# Key.net
KiCad netlist of a schematic drawn in EAGLE
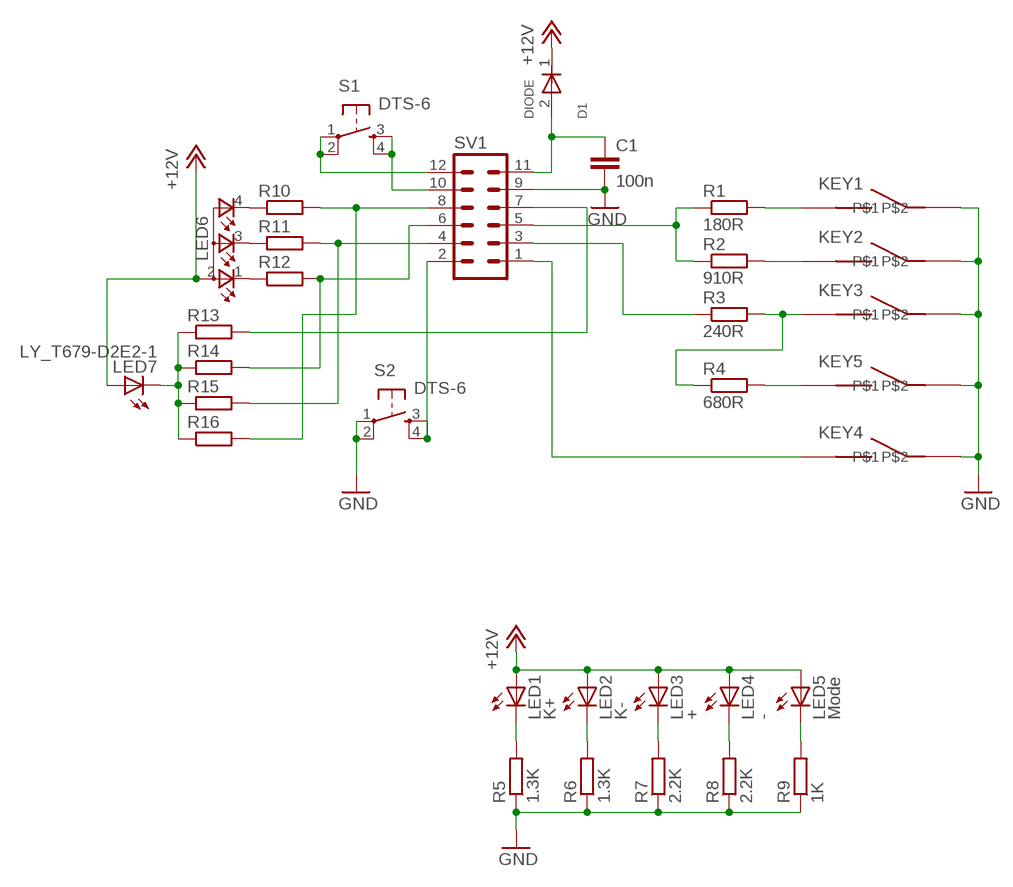
[diagram p0: schematic, sheet 1]

(export (version "E")
  (design (tool "Eeschema 10.0.6"))
  (components
    (comp (ref "C1")
      (value "100n")
      (footprint "eagle-import:C0805K")
      (libsource (lib "eagle-import") (part "C-EUC0805K"))
    )
    (comp (ref "D1")
      (value "DIODE")
      (footprint "eagle-import:SOD80")
      (libsource (lib "eagle-import") (part "DIODE"))
    )
    (comp (ref "KEY1")
      (value "PRINT_KEYPRINTED-KEY")
      (footprint "eagle-import:PRINT_KEY")
      (libsource (lib "eagle-import") (part "PRINT_KEYPRINTED-KEY"))
    )
    (comp (ref "KEY2")
      (value "PRINT_KEYPRINTED-KEY")
      (footprint "eagle-import:PRINT_KEY")
      (libsource (lib "eagle-import") (part "PRINT_KEYPRINTED-KEY"))
    )
    (comp (ref "KEY3")
      (value "PRINT_KEYPRINTED-KEY")
      (footprint "eagle-import:PRINT_KEY")
      (libsource (lib "eagle-import") (part "PRINT_KEYPRINTED-KEY"))
    )
    (comp (ref "KEY4")
      (value "PRINT_KEYPRINTED-KEY")
      (footprint "eagle-import:PRINT_KEY")
      (libsource (lib "eagle-import") (part "PRINT_KEYPRINTED-KEY"))
    )
    (comp (ref "KEY5")
      (value "PRINT_KEYPRINTED-KEY")
      (footprint "eagle-import:PRINT_KEY")
      (libsource (lib "eagle-import") (part "PRINT_KEYPRINTED-KEY"))
    )
    (comp (ref "LED1")
      (value "K+")
      (footprint "eagle-import:PLCC2")
      (libsource (lib "eagle-import") (part "_T679-?-1D2E2LY"))
    )
    (comp (ref "LED2")
      (value "K-")
      (footprint "eagle-import:PLCC2")
      (libsource (lib "eagle-import") (part "_T679-?-1D2E2LY"))
    )
    (comp (ref "LED3")
      (value "+")
      (footprint "eagle-import:PLCC2")
      (libsource (lib "eagle-import") (part "_T679-?-1D2E2LY"))
    )
    (comp (ref "LED4")
      (value "-")
      (footprint "eagle-import:PLCC2")
      (libsource (lib "eagle-import") (part "_T679-?-1D2E2LY"))
    )
    (comp (ref "LED5")
      (value "Mode")
      (footprint "eagle-import:PLCC2")
      (libsource (lib "eagle-import") (part "_T679-?-1D2E2LY"))
    )
    (comp (ref "LED6")
      (value "TOPLED-3")
      (footprint "eagle-import:P-LCC-4-3")
      (libsource (lib "eagle-import") (part "TOPLED-3"))
    )
    (comp (ref "LED7")
      (value "LY_T679-D2E2-1")
      (footprint "eagle-import:PLCC2")
      (libsource (lib "eagle-import") (part "_T679-?-1D2E2LY"))
    )
    (comp (ref "R1")
      (value "180R")
      (footprint "eagle-import:R1206")
      (libsource (lib "eagle-import") (part "R-EU_R1206"))
    )
    (comp (ref "R2")
      (value "910R")
      (footprint "eagle-import:R1206")
      (libsource (lib "eagle-import") (part "R-EU_R1206"))
    )
    (comp (ref "R3")
      (value "240R")
      (footprint "eagle-import:R1206")
      (libsource (lib "eagle-import") (part "R-EU_R1206"))
    )
    (comp (ref "R4")
      (value "680R")
      (footprint "eagle-import:R1206")
      (libsource (lib "eagle-import") (part "R-EU_R1206"))
    )
    (comp (ref "R5")
      (value "1.3K")
      (footprint "eagle-import:R1206")
      (libsource (lib "eagle-import") (part "R-EU_R1206"))
    )
    (comp (ref "R6")
      (value "1.3K")
      (footprint "eagle-import:R1206")
      (libsource (lib "eagle-import") (part "R-EU_R1206"))
    )
    (comp (ref "R7")
      (value "2.2K")
      (footprint "eagle-import:R1206")
      (libsource (lib "eagle-import") (part "R-EU_R1206"))
    )
    (comp (ref "R8")
      (value "2.2K")
      (footprint "eagle-import:R1206")
      (libsource (lib "eagle-import") (part "R-EU_R1206"))
    )
    (comp (ref "R9")
      (value "1K")
      (footprint "eagle-import:R1206")
      (libsource (lib "eagle-import") (part "R-EU_R1206"))
    )
    (comp (ref "R10")
      (value "R-EU_R0603")
      (footprint "eagle-import:R0603")
      (libsource (lib "eagle-import") (part "R-EU_R0603"))
    )
    (comp (ref "R11")
      (value "R-EU_R0603")
      (footprint "eagle-import:R0603")
      (libsource (lib "eagle-import") (part "R-EU_R0603"))
    )
    (comp (ref "R12")
      (value "R-EU_R0603")
      (footprint "eagle-import:R0603")
      (libsource (lib "eagle-import") (part "R-EU_R0603"))
    )
    (comp (ref "R13")
      (value "R-EU_R0603")
      (footprint "eagle-import:R0603")
      (libsource (lib "eagle-import") (part "R-EU_R0603"))
    )
    (comp (ref "R14")
      (value "R-EU_R0603")
      (footprint "eagle-import:R0603")
      (libsource (lib "eagle-import") (part "R-EU_R0603"))
    )
    (comp (ref "R15")
      (value "R-EU_R0603")
      (footprint "eagle-import:R0603")
      (libsource (lib "eagle-import") (part "R-EU_R0603"))
    )
    (comp (ref "R16")
      (value "R-EU_R0603")
      (footprint "eagle-import:R0603")
      (libsource (lib "eagle-import") (part "R-EU_R0603"))
    )
    (comp (ref "S1")
      (value "DTS-6")
      (footprint "eagle-import:DTS-6")
      (libsource (lib "eagle-import") (part "DTS-6"))
    )
    (comp (ref "S2")
      (value "DTS-6")
      (footprint "eagle-import:DTS-6")
      (libsource (lib "eagle-import") (part "DTS-6"))
    )
    (comp (ref "SV1")
      (value "MA06-2")
      (footprint "eagle-import:MA06-2")
      (libsource (lib "eagle-import") (part "MA06-2"))
    )
  )
  (nets
    (net (code "1") (name "+12V") (class "Default")
      (node (ref "D1") (pin "1") (pinfunction "KATOD_1") (pintype "power_in"))
      (node (ref "LED1") (pin "A") (pinfunction "A_A") (pintype "passive"))
      (node (ref "LED2") (pin "A") (pinfunction "A_A") (pintype "passive"))
      (node (ref "LED3") (pin "A") (pinfunction "A_A") (pintype "passive"))
      (node (ref "LED4") (pin "A") (pinfunction "A_A") (pintype "passive"))
      (node (ref "LED5") (pin "A") (pinfunction "A_A") (pintype "passive"))
      (node (ref "LED6") (pin "2") (pinfunction "A2_2") (pintype "passive"))
      (node (ref "LED7") (pin "A") (pinfunction "A_A") (pintype "passive"))
    )
    (net (code "2") (name "GND") (class "Default")
      (node (ref "C1") (pin "2") (pinfunction "2_2") (pintype "passive"))
      (node (ref "KEY1") (pin "P$2") (pinfunction "P$2_P$2") (pintype "bidirectional"))
      (node (ref "KEY2") (pin "P$2") (pinfunction "P$2_P$2") (pintype "bidirectional"))
      (node (ref "KEY3") (pin "P$2") (pinfunction "P$2_P$2") (pintype "bidirectional"))
      (node (ref "KEY4") (pin "P$2") (pinfunction "P$2_P$2") (pintype "bidirectional"))
      (node (ref "KEY5") (pin "P$2") (pinfunction "P$2_P$2") (pintype "bidirectional"))
      (node (ref "R5") (pin "1") (pinfunction "1_1") (pintype "passive"))
      (node (ref "R6") (pin "1") (pinfunction "1_1") (pintype "passive"))
      (node (ref "R7") (pin "1") (pinfunction "1_1") (pintype "passive"))
      (node (ref "R8") (pin "1") (pinfunction "1_1") (pintype "passive"))
      (node (ref "R9") (pin "1") (pinfunction "1_1") (pintype "passive"))
      (node (ref "S2") (pin "1") (pinfunction "1_1") (pintype "passive"))
      (node (ref "S2") (pin "2") (pinfunction "2_2") (pintype "passive"))
      (node (ref "SV1") (pin "9") (pinfunction "9_9") (pintype "passive"))
    )
    (net (code "3") (name "Net-(D1-ANOD)") (class "Default")
      (node (ref "C1") (pin "1") (pinfunction "1_1") (pintype "passive"))
      (node (ref "D1") (pin "2") (pinfunction "ANOD_2") (pintype "power_in"))
      (node (ref "SV1") (pin "11") (pinfunction "11_11") (pintype "passive"))
    )
    (net (code "4") (name "Net-(KEY1-PadP$1)") (class "Default")
      (node (ref "KEY1") (pin "P$1") (pinfunction "P$1_P$1") (pintype "bidirectional"))
      (node (ref "R1") (pin "2") (pinfunction "2_2") (pintype "passive"))
    )
    (net (code "5") (name "Net-(KEY2-PadP$1)") (class "Default")
      (node (ref "KEY2") (pin "P$1") (pinfunction "P$1_P$1") (pintype "bidirectional"))
      (node (ref "R2") (pin "2") (pinfunction "2_2") (pintype "passive"))
    )
    (net (code "6") (name "Net-(KEY3-PadP$1)") (class "Default")
      (node (ref "KEY3") (pin "P$1") (pinfunction "P$1_P$1") (pintype "bidirectional"))
      (node (ref "R3") (pin "2") (pinfunction "2_2") (pintype "passive"))
      (node (ref "R4") (pin "1") (pinfunction "1_1") (pintype "passive"))
    )
    (net (code "7") (name "Net-(KEY4-PadP$1)") (class "Default")
      (node (ref "KEY4") (pin "P$1") (pinfunction "P$1_P$1") (pintype "bidirectional"))
      (node (ref "SV1") (pin "1") (pinfunction "1_1") (pintype "passive"))
    )
    (net (code "8") (name "Net-(KEY5-PadP$1)") (class "Default")
      (node (ref "KEY5") (pin "P$1") (pinfunction "P$1_P$1") (pintype "bidirectional"))
      (node (ref "R4") (pin "2") (pinfunction "2_2") (pintype "passive"))
    )
    (net (code "9") (name "Net-(LED1-PadC)") (class "Default")
      (node (ref "LED1") (pin "C") (pinfunction "C_C") (pintype "passive"))
      (node (ref "R5") (pin "2") (pinfunction "2_2") (pintype "passive"))
    )
    (net (code "10") (name "Net-(LED2-PadC)") (class "Default")
      (node (ref "LED2") (pin "C") (pinfunction "C_C") (pintype "passive"))
      (node (ref "R6") (pin "2") (pinfunction "2_2") (pintype "passive"))
    )
    (net (code "11") (name "Net-(LED3-PadC)") (class "Default")
      (node (ref "LED3") (pin "C") (pinfunction "C_C") (pintype "passive"))
      (node (ref "R7") (pin "2") (pinfunction "2_2") (pintype "passive"))
    )
    (net (code "12") (name "Net-(LED4-PadC)") (class "Default")
      (node (ref "LED4") (pin "C") (pinfunction "C_C") (pintype "passive"))
      (node (ref "R8") (pin "2") (pinfunction "2_2") (pintype "passive"))
    )
    (net (code "13") (name "Net-(LED5-PadC)") (class "Default")
      (node (ref "LED5") (pin "C") (pinfunction "C_C") (pintype "passive"))
      (node (ref "R9") (pin "2") (pinfunction "2_2") (pintype "passive"))
    )
    (net (code "14") (name "Net-(LED6-CBLUE)") (class "Default")
      (node (ref "LED6") (pin "3") (pinfunction "CBLUE_3") (pintype "passive"))
      (node (ref "R11") (pin "1") (pinfunction "1_1") (pintype "passive"))
    )
    (net (code "15") (name "Net-(LED6-CGREEN)") (class "Default")
      (node (ref "LED6") (pin "4") (pinfunction "CGREEN_4") (pintype "passive"))
      (node (ref "R10") (pin "1") (pinfunction "1_1") (pintype "passive"))
    )
    (net (code "16") (name "Net-(LED6-CRED)") (class "Default")
      (node (ref "LED6") (pin "1") (pinfunction "CRED_1") (pintype "passive"))
      (node (ref "R12") (pin "1") (pinfunction "1_1") (pintype "passive"))
    )
    (net (code "17") (name "Net-(LED7-PadC)") (class "Default")
      (node (ref "LED7") (pin "C") (pinfunction "C_C") (pintype "passive"))
      (node (ref "R13") (pin "1") (pinfunction "1_1") (pintype "passive"))
      (node (ref "R14") (pin "1") (pinfunction "1_1") (pintype "passive"))
      (node (ref "R15") (pin "1") (pinfunction "1_1") (pintype "passive"))
      (node (ref "R16") (pin "1") (pinfunction "1_1") (pintype "passive"))
    )
    (net (code "18") (name "Net-(R1-Pad1)") (class "Default")
      (node (ref "R1") (pin "1") (pinfunction "1_1") (pintype "passive"))
      (node (ref "R2") (pin "1") (pinfunction "1_1") (pintype "passive"))
      (node (ref "SV1") (pin "5") (pinfunction "5_5") (pintype "passive"))
    )
    (net (code "19") (name "Net-(R3-Pad1)") (class "Default")
      (node (ref "R3") (pin "1") (pinfunction "1_1") (pintype "passive"))
      (node (ref "SV1") (pin "3") (pinfunction "3_3") (pintype "passive"))
    )
    (net (code "20") (name "Net-(R10-Pad2)") (class "Default")
      (node (ref "R10") (pin "2") (pinfunction "2_2") (pintype "passive"))
      (node (ref "R16") (pin "2") (pinfunction "2_2") (pintype "passive"))
      (node (ref "SV1") (pin "8") (pinfunction "8_8") (pintype "passive"))
    )
    (net (code "21") (name "Net-(R11-Pad2)") (class "Default")
      (node (ref "R11") (pin "2") (pinfunction "2_2") (pintype "passive"))
      (node (ref "R15") (pin "2") (pinfunction "2_2") (pintype "passive"))
      (node (ref "SV1") (pin "4") (pinfunction "4_4") (pintype "passive"))
    )
    (net (code "22") (name "Net-(R12-Pad2)") (class "Default")
      (node (ref "R12") (pin "2") (pinfunction "2_2") (pintype "passive"))
      (node (ref "R14") (pin "2") (pinfunction "2_2") (pintype "passive"))
      (node (ref "SV1") (pin "6") (pinfunction "6_6") (pintype "passive"))
    )
    (net (code "23") (name "Net-(R13-Pad2)") (class "Default")
      (node (ref "R13") (pin "2") (pinfunction "2_2") (pintype "passive"))
      (node (ref "SV1") (pin "7") (pinfunction "7_7") (pintype "passive"))
    )
    (net (code "24") (name "Net-(S1-Pad1)") (class "Default")
      (node (ref "S1") (pin "1") (pinfunction "1_1") (pintype "passive"))
      (node (ref "S1") (pin "2") (pinfunction "2_2") (pintype "passive"))
      (node (ref "SV1") (pin "12") (pinfunction "12_12") (pintype "passive"))
    )
    (net (code "25") (name "Net-(S1-Pad3)") (class "Default")
      (node (ref "S1") (pin "3") (pinfunction "3_3") (pintype "passive"))
      (node (ref "S1") (pin "4") (pinfunction "4_4") (pintype "passive"))
      (node (ref "SV1") (pin "10") (pinfunction "10_10") (pintype "passive"))
    )
    (net (code "26") (name "Net-(S2-Pad3)") (class "Default")
      (node (ref "S2") (pin "3") (pinfunction "3_3") (pintype "passive"))
      (node (ref "S2") (pin "4") (pinfunction "4_4") (pintype "passive"))
      (node (ref "SV1") (pin "2") (pinfunction "2_2") (pintype "passive"))
    )
  )
)
